# DVforArduino.net
KiCad netlist of a schematic drawn in EAGLE
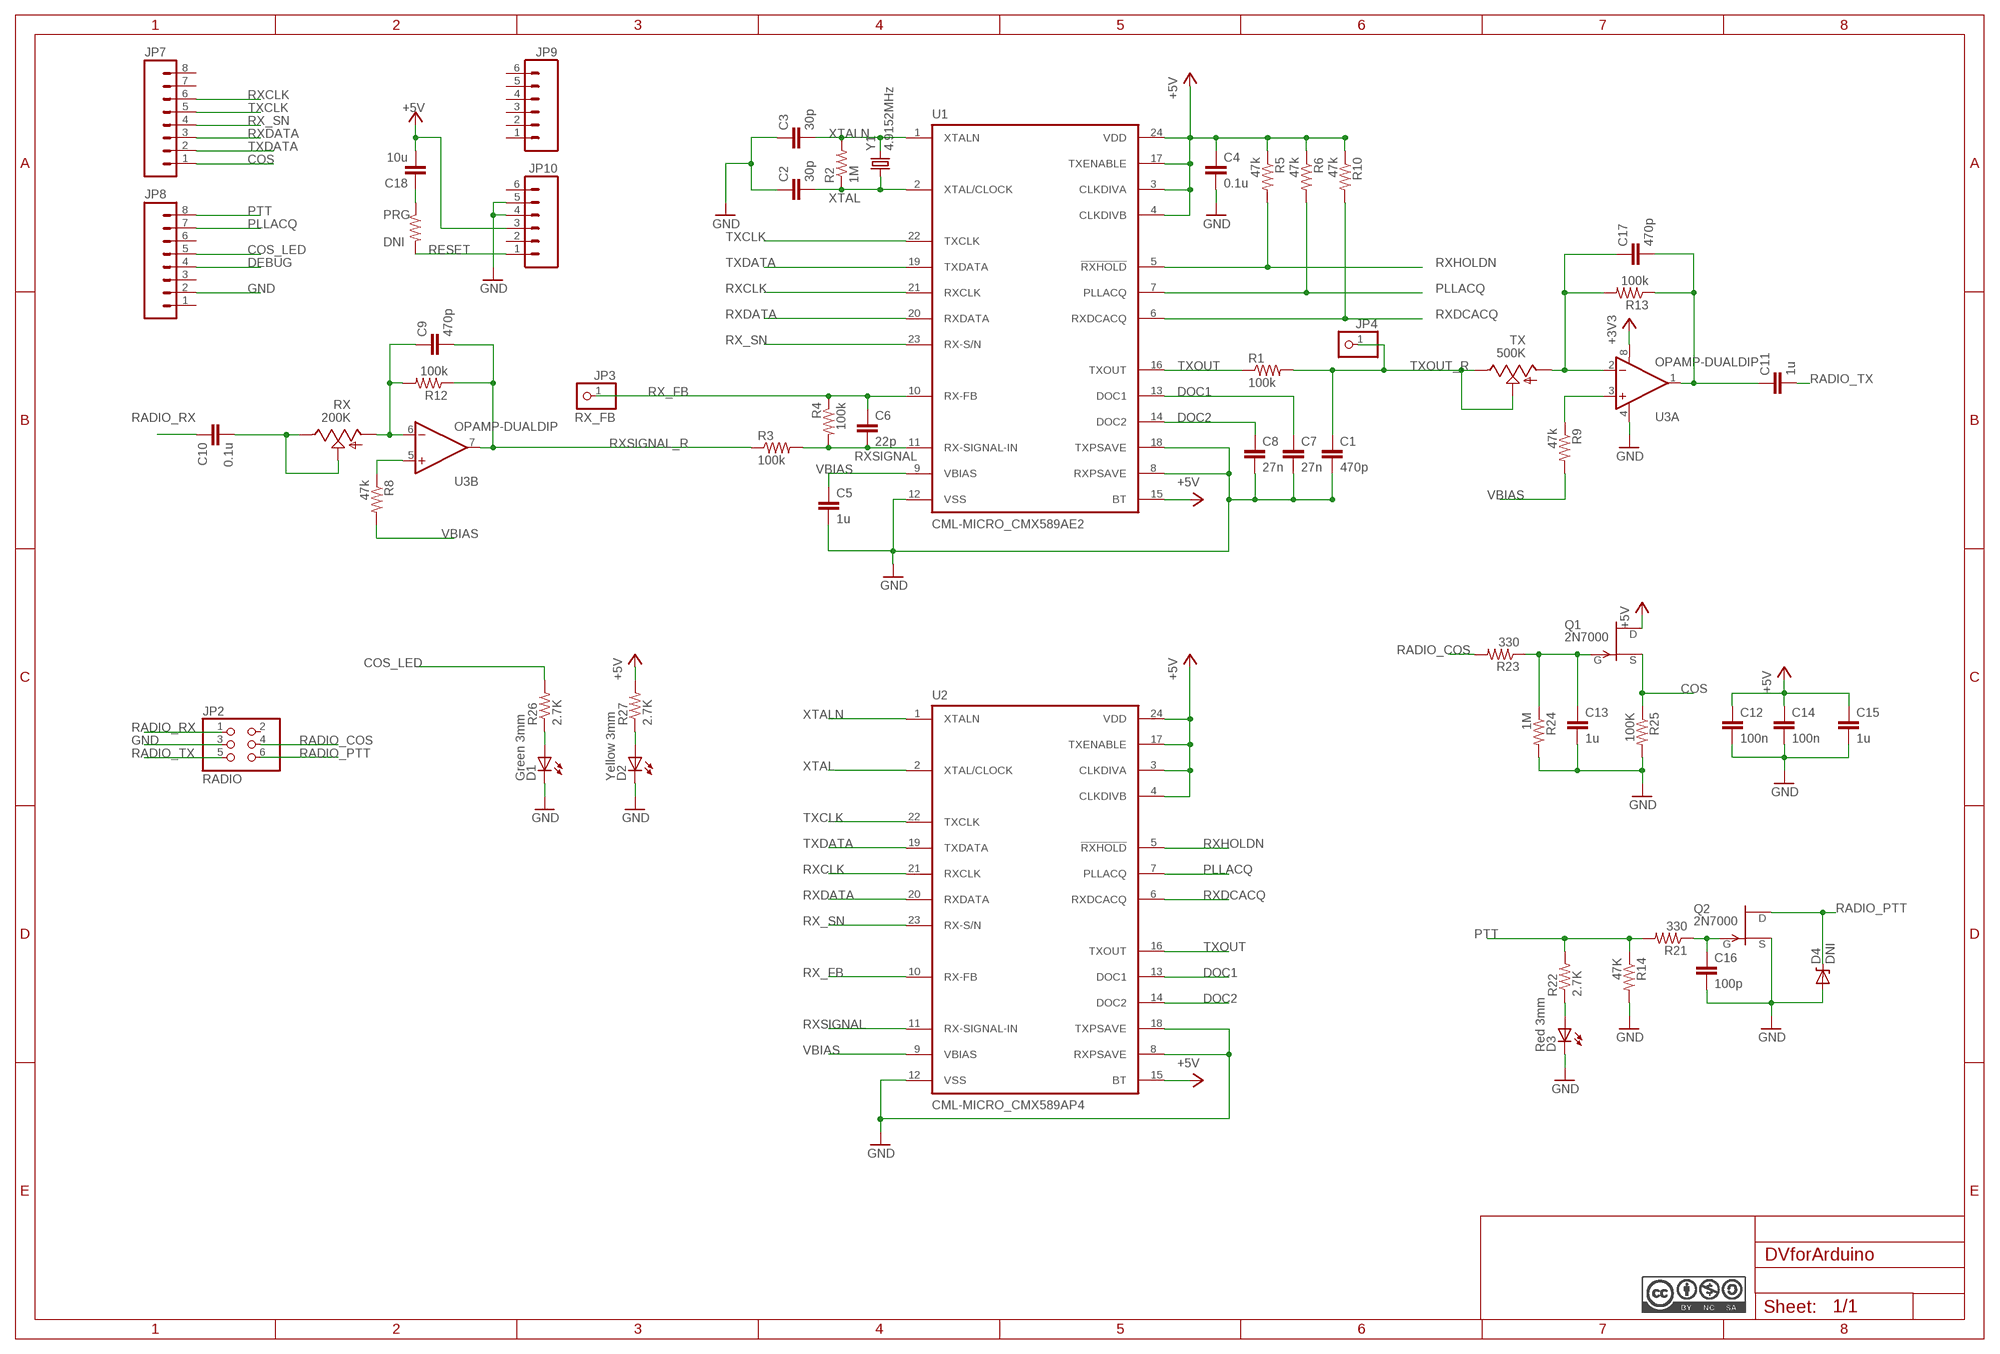
[diagram p0: schematic, sheet 1]

(export (version "E")
  (design (tool "Eeschema 10.0.6"))
  (components
    (comp (ref "C1")
      (value "470p")
      (footprint "eagle-import:C2.5-3")
      (libsource (lib "eagle-import") (part "C2,5-3"))
    )
    (comp (ref "C2")
      (value "30p")
      (footprint "eagle-import:C2.5-3")
      (libsource (lib "eagle-import") (part "C2,5-3"))
    )
    (comp (ref "C3")
      (value "30p")
      (footprint "eagle-import:C2.5-3")
      (libsource (lib "eagle-import") (part "C2,5-3"))
    )
    (comp (ref "C4")
      (value "0.1u")
      (footprint "eagle-import:C2.5-3")
      (libsource (lib "eagle-import") (part "C2,5-3"))
    )
    (comp (ref "C5")
      (value "1u")
      (footprint "eagle-import:C2.5-3")
      (libsource (lib "eagle-import") (part "C2,5-3"))
    )
    (comp (ref "C6")
      (value "22p")
      (footprint "eagle-import:C2.5-3")
      (libsource (lib "eagle-import") (part "C2,5-3"))
    )
    (comp (ref "C7")
      (value "27n")
      (footprint "eagle-import:C2.5-3")
      (libsource (lib "eagle-import") (part "C2,5-3"))
    )
    (comp (ref "C8")
      (value "27n")
      (footprint "eagle-import:C2.5-3")
      (libsource (lib "eagle-import") (part "C2,5-3"))
    )
    (comp (ref "C9")
      (value "470p")
      (footprint "eagle-import:C2.5-3")
      (libsource (lib "eagle-import") (part "C2,5-3"))
    )
    (comp (ref "C10")
      (value "0.1u")
      (footprint "eagle-import:C2.5-3")
      (libsource (lib "eagle-import") (part "C2,5-3"))
    )
    (comp (ref "C11")
      (value "1u")
      (footprint "eagle-import:C2.5-3")
      (libsource (lib "eagle-import") (part "C2,5-3"))
    )
    (comp (ref "C12")
      (value "100n")
      (footprint "eagle-import:C2.5-3")
      (libsource (lib "eagle-import") (part "C2,5-3"))
    )
    (comp (ref "C13")
      (value "1u")
      (footprint "eagle-import:C2.5-3")
      (libsource (lib "eagle-import") (part "C2,5-3"))
    )
    (comp (ref "C14")
      (value "100n")
      (footprint "eagle-import:C2.5-3")
      (libsource (lib "eagle-import") (part "C2,5-3"))
    )
    (comp (ref "C15")
      (value "1u")
      (footprint "eagle-import:C2.5-3")
      (libsource (lib "eagle-import") (part "C2,5-3"))
    )
    (comp (ref "C16")
      (value "100p")
      (footprint "eagle-import:C2.5-3")
      (libsource (lib "eagle-import") (part "C2,5-3"))
    )
    (comp (ref "C17")
      (value "470p")
      (footprint "eagle-import:C2.5-3")
      (libsource (lib "eagle-import") (part "C2,5-3"))
    )
    (comp (ref "C18")
      (value "10u")
      (footprint "eagle-import:C2.5-3")
      (libsource (lib "eagle-import") (part "C2,5-3"))
    )
    (comp (ref "D1")
      (value "Green 3mm")
      (footprint "eagle-import:LED3MM")
      (libsource (lib "eagle-import") (part "LED3MM"))
    )
    (comp (ref "D2")
      (value "Yellow 3mm")
      (footprint "eagle-import:LED3MM")
      (libsource (lib "eagle-import") (part "LED3MM"))
    )
    (comp (ref "D3")
      (value "Red 3mm")
      (footprint "eagle-import:LED3MM")
      (libsource (lib "eagle-import") (part "LED3MM"))
    )
    (comp (ref "D4")
      (value "DNI")
      (footprint "eagle-import:DIODE-ZENER")
      (libsource (lib "eagle-import") (part "DIODE-ZENERPTH"))
    )
    (comp (ref "JP2")
      (value "RADIO")
      (footprint "eagle-import:2X03_ROUND_70MIL")
      (libsource (lib "eagle-import") (part "HEADER-2X3"))
    )
    (comp (ref "JP3")
      (value "RX_FB")
      (footprint "eagle-import:1X01_ROUND")
      (libsource (lib "eagle-import") (part "HEADER-1X1ROUND"))
    )
    (comp (ref "JP4")
      (value "HEADER-1X1ROUND")
      (footprint "eagle-import:1X01_ROUND")
      (libsource (lib "eagle-import") (part "HEADER-1X1ROUND"))
    )
    (comp (ref "JP7")
      (value "M081X08")
      (footprint "eagle-import:1X08")
      (libsource (lib "eagle-import") (part "M081X08"))
    )
    (comp (ref "JP8")
      (value "M081X08")
      (footprint "eagle-import:1X08")
      (libsource (lib "eagle-import") (part "M081X08"))
    )
    (comp (ref "JP9")
      (value "M06SIP")
      (footprint "eagle-import:1X06")
      (libsource (lib "eagle-import") (part "M06SIP"))
    )
    (comp (ref "JP10")
      (value "M06SIP")
      (footprint "eagle-import:1X06")
      (libsource (lib "eagle-import") (part "M06SIP"))
    )
    (comp (ref "PRG")
      (value "DNI")
      (footprint "eagle-import:0204V")
      (libsource (lib "eagle-import") (part "R-US_0204/2V"))
    )
    (comp (ref "Q1")
      (value "2N7000")
      (footprint "eagle-import:TO92")
      (libsource (lib "eagle-import") (part "2N3819"))
    )
    (comp (ref "Q2")
      (value "2N7000")
      (footprint "eagle-import:TO92")
      (libsource (lib "eagle-import") (part "2N3819"))
    )
    (comp (ref "R1")
      (value "100k")
      (footprint "eagle-import:0204V")
      (libsource (lib "eagle-import") (part "R-US_0204/2V"))
    )
    (comp (ref "R2")
      (value "1M")
      (footprint "eagle-import:0204V")
      (libsource (lib "eagle-import") (part "R-US_0204/2V"))
    )
    (comp (ref "R3")
      (value "100k")
      (footprint "eagle-import:0204V")
      (libsource (lib "eagle-import") (part "R-US_0204/2V"))
    )
    (comp (ref "R4")
      (value "100k")
      (footprint "eagle-import:0204V")
      (libsource (lib "eagle-import") (part "R-US_0204/2V"))
    )
    (comp (ref "R5")
      (value "47k")
      (footprint "eagle-import:0204V")
      (libsource (lib "eagle-import") (part "R-US_0204/2V"))
    )
    (comp (ref "R6")
      (value "47k")
      (footprint "eagle-import:0204V")
      (libsource (lib "eagle-import") (part "R-US_0204/2V"))
    )
    (comp (ref "R8")
      (value "47k")
      (footprint "eagle-import:0204V")
      (libsource (lib "eagle-import") (part "R-US_0204/2V"))
    )
    (comp (ref "R9")
      (value "47k")
      (footprint "eagle-import:0204V")
      (libsource (lib "eagle-import") (part "R-US_0204/2V"))
    )
    (comp (ref "R10")
      (value "47k")
      (footprint "eagle-import:0204V")
      (libsource (lib "eagle-import") (part "R-US_0204/2V"))
    )
    (comp (ref "R12")
      (value "100k")
      (footprint "eagle-import:0204V")
      (libsource (lib "eagle-import") (part "R-US_0204/2V"))
    )
    (comp (ref "R13")
      (value "100k")
      (footprint "eagle-import:0204V")
      (libsource (lib "eagle-import") (part "R-US_0204/2V"))
    )
    (comp (ref "R14")
      (value "47K")
      (footprint "eagle-import:0204V")
      (libsource (lib "eagle-import") (part "R-US_0204/2V"))
    )
    (comp (ref "R21")
      (value "330")
      (footprint "eagle-import:0204V")
      (libsource (lib "eagle-import") (part "R-US_0204/2V"))
    )
    (comp (ref "R22")
      (value "2.7K")
      (footprint "eagle-import:0204V")
      (libsource (lib "eagle-import") (part "R-US_0204/2V"))
    )
    (comp (ref "R23")
      (value "330")
      (footprint "eagle-import:0204V")
      (libsource (lib "eagle-import") (part "R-US_0204/2V"))
    )
    (comp (ref "R24")
      (value "1M")
      (footprint "eagle-import:0204V")
      (libsource (lib "eagle-import") (part "R-US_0204/2V"))
    )
    (comp (ref "R25")
      (value "100K")
      (footprint "eagle-import:0204V")
      (libsource (lib "eagle-import") (part "R-US_0204/2V"))
    )
    (comp (ref "R26")
      (value "2.7K")
      (footprint "eagle-import:0204V")
      (libsource (lib "eagle-import") (part "R-US_0204/2V"))
    )
    (comp (ref "R27")
      (value "2.7K")
      (footprint "eagle-import:0204V")
      (libsource (lib "eagle-import") (part "R-US_0204/2V"))
    )
    (comp (ref "RX")
      (value "200K")
      (footprint "eagle-import:B25P")
      (libsource (lib "eagle-import") (part "TRIM_US-B25P"))
    )
    (comp (ref "TX")
      (value "500K")
      (footprint "eagle-import:B25P")
      (libsource (lib "eagle-import") (part "TRIM_US-B25P"))
    )
    (comp (ref "U1")
      (value "CML-MICRO_CMX589AE2")
      (footprint "eagle-import:AIS_MK2_CML-MICRO_TSSOP24")
      (libsource (lib "eagle-import") (part "mylibrary_AIS_MK2_CML-MICRO_CMX589AE2"))
    )
    (comp (ref "U2")
      (value "CML-MICRO_CMX589AP4")
      (footprint "eagle-import:AIS_MK2_CML-MICRO_DIL24-6")
      (libsource (lib "eagle-import") (part "AIS_MK2_CML-MICRO_CMX589AP4"))
    )
    (comp (ref "U3")
      (value "OPAMP-DUALDIP")
      (footprint "eagle-import:DIP08")
      (libsource (lib "eagle-import") (part "OPAMP-DUALDIP"))
    )
    (comp (ref "Y1")
      (value "4.9152MHz")
      (footprint "eagle-import:HC49US")
      (libsource (lib "eagle-import") (part "CRYSTALHC49US"))
    )
  )
  (nets
    (net (code "1") (name "+3V3") (class "Default")
      (node (ref "C12") (pin "1") (pinfunction "1_1") (pintype "passive"))
      (node (ref "C14") (pin "1") (pinfunction "1_1") (pintype "passive"))
      (node (ref "C15") (pin "1") (pinfunction "1_1") (pintype "passive"))
      (node (ref "C18") (pin "2") (pinfunction "2_2") (pintype "passive"))
      (node (ref "C4") (pin "1") (pinfunction "1_1") (pintype "passive"))
      (node (ref "JP10") (pin "3") (pinfunction "3_3") (pintype "passive"))
      (node (ref "Q1") (pin "1") (pinfunction "D_1") (pintype "passive"))
      (node (ref "R10") (pin "1") (pinfunction "1_1") (pintype "passive"))
      (node (ref "R27") (pin "2") (pinfunction "2_2") (pintype "passive"))
      (node (ref "R5") (pin "1") (pinfunction "1_1") (pintype "passive"))
      (node (ref "R6") (pin "1") (pinfunction "1_1") (pintype "passive"))
      (node (ref "U1") (pin "15") (pinfunction "BT_15") (pintype "input"))
      (node (ref "U1") (pin "17") (pinfunction "TXENABLE_17") (pintype "input"))
      (node (ref "U1") (pin "24") (pinfunction "VDD_24") (pintype "power_in"))
      (node (ref "U1") (pin "3") (pinfunction "CLKDIVA_3") (pintype "input"))
      (node (ref "U1") (pin "4") (pinfunction "CLKDIVB_4") (pintype "input"))
      (node (ref "U2") (pin "15") (pinfunction "BT_15") (pintype "input"))
      (node (ref "U2") (pin "17") (pinfunction "TXENABLE_17") (pintype "input"))
      (node (ref "U2") (pin "24") (pinfunction "VDD_24") (pintype "power_in"))
      (node (ref "U2") (pin "3") (pinfunction "CLKDIVA_3") (pintype "input"))
      (node (ref "U2") (pin "4") (pinfunction "CLKDIVB_4") (pintype "input"))
      (node (ref "U3") (pin "8") (pinfunction "V+_8") (pintype "power_in"))
    )
    (net (code "2") (name "/COS") (class "Default")
      (node (ref "JP7") (pin "1") (pinfunction "1_1") (pintype "passive"))
      (node (ref "Q1") (pin "3") (pinfunction "S_3") (pintype "passive"))
      (node (ref "R25") (pin "1") (pinfunction "1_1") (pintype "passive"))
    )
    (net (code "3") (name "/COS_LED") (class "Default")
      (node (ref "JP8") (pin "5") (pinfunction "5_5") (pintype "passive"))
      (node (ref "R26") (pin "2") (pinfunction "2_2") (pintype "passive"))
    )
    (net (code "4") (name "/DEBUG") (class "Default")
      (node (ref "JP8") (pin "4") (pinfunction "4_4") (pintype "passive"))
    )
    (net (code "5") (name "/DOC1") (class "Default")
      (node (ref "C7") (pin "1") (pinfunction "1_1") (pintype "passive"))
      (node (ref "U1") (pin "13") (pinfunction "DOC1_13") (pintype "passive"))
      (node (ref "U2") (pin "13") (pinfunction "DOC1_13") (pintype "passive"))
    )
    (net (code "6") (name "/DOC2") (class "Default")
      (node (ref "C8") (pin "1") (pinfunction "1_1") (pintype "passive"))
      (node (ref "U1") (pin "14") (pinfunction "DOC2_14") (pintype "passive"))
      (node (ref "U2") (pin "14") (pinfunction "DOC2_14") (pintype "passive"))
    )
    (net (code "7") (name "/PLLACQ") (class "Default")
      (node (ref "JP8") (pin "7") (pinfunction "7_7") (pintype "passive"))
      (node (ref "R6") (pin "2") (pinfunction "2_2") (pintype "passive"))
      (node (ref "U1") (pin "7") (pinfunction "PLLACQ_7") (pintype "input"))
      (node (ref "U2") (pin "7") (pinfunction "PLLACQ_7") (pintype "input"))
    )
    (net (code "8") (name "/PTT") (class "Default")
      (node (ref "JP8") (pin "8") (pinfunction "8_8") (pintype "passive"))
      (node (ref "R14") (pin "1") (pinfunction "1_1") (pintype "passive"))
      (node (ref "R21") (pin "2") (pinfunction "2_2") (pintype "passive"))
      (node (ref "R22") (pin "2") (pinfunction "2_2") (pintype "passive"))
    )
    (net (code "9") (name "/RADIO_COS") (class "Default")
      (node (ref "JP2") (pin "4") (pinfunction "4_4") (pintype "passive"))
      (node (ref "R23") (pin "2") (pinfunction "2_2") (pintype "passive"))
    )
    (net (code "10") (name "/RADIO_PTT") (class "Default")
      (node (ref "D4") (pin "P$1") (pinfunction "C_P$1") (pintype "passive"))
      (node (ref "JP2") (pin "6") (pinfunction "6_6") (pintype "passive"))
      (node (ref "Q2") (pin "1") (pinfunction "D_1") (pintype "passive"))
    )
    (net (code "11") (name "/RADIO_RX") (class "Default")
      (node (ref "C10") (pin "1") (pinfunction "1_1") (pintype "passive"))
      (node (ref "JP2") (pin "1") (pinfunction "1_1") (pintype "passive"))
    )
    (net (code "12") (name "/RADIO_TX") (class "Default")
      (node (ref "C11") (pin "2") (pinfunction "2_2") (pintype "passive"))
      (node (ref "JP2") (pin "5") (pinfunction "5_5") (pintype "passive"))
    )
    (net (code "13") (name "/RESET") (class "Default")
      (node (ref "JP10") (pin "1") (pinfunction "1_1") (pintype "passive"))
      (node (ref "PRG") (pin "2") (pinfunction "2_2") (pintype "passive"))
    )
    (net (code "14") (name "/RXCLK") (class "Default")
      (node (ref "JP7") (pin "6") (pinfunction "6_6") (pintype "passive"))
      (node (ref "U1") (pin "21") (pinfunction "RXCLK_21") (pintype "output"))
      (node (ref "U2") (pin "21") (pinfunction "RXCLK_21") (pintype "output"))
    )
    (net (code "15") (name "/RXDATA") (class "Default")
      (node (ref "JP7") (pin "3") (pinfunction "3_3") (pintype "passive"))
      (node (ref "U1") (pin "20") (pinfunction "RXDATA_20") (pintype "output"))
      (node (ref "U2") (pin "20") (pinfunction "RXDATA_20") (pintype "output"))
    )
    (net (code "16") (name "/RXDCACQ") (class "Default")
      (node (ref "R10") (pin "2") (pinfunction "2_2") (pintype "passive"))
      (node (ref "U1") (pin "6") (pinfunction "RXDCACQ_6") (pintype "input"))
      (node (ref "U2") (pin "6") (pinfunction "RXDCACQ_6") (pintype "input"))
    )
    (net (code "17") (name "/RXHOLDN") (class "Default")
      (node (ref "R5") (pin "2") (pinfunction "2_2") (pintype "passive"))
      (node (ref "U1") (pin "5") (pinfunction "~{RXHOLD}_5") (pintype "input"))
      (node (ref "U2") (pin "5") (pinfunction "~{RXHOLD}_5") (pintype "input"))
    )
    (net (code "18") (name "/RXSIGNAL") (class "Default")
      (node (ref "C6") (pin "2") (pinfunction "2_2") (pintype "passive"))
      (node (ref "R3") (pin "2") (pinfunction "2_2") (pintype "passive"))
      (node (ref "R4") (pin "2") (pinfunction "2_2") (pintype "passive"))
      (node (ref "U1") (pin "11") (pinfunction "RX-SIGNAL-IN_11") (pintype "input"))
      (node (ref "U2") (pin "11") (pinfunction "RX-SIGNAL-IN_11") (pintype "input"))
    )
    (net (code "19") (name "/RXSIGNAL_R") (class "Default")
      (node (ref "C9") (pin "2") (pinfunction "2_2") (pintype "passive"))
      (node (ref "R12") (pin "1") (pinfunction "1_1") (pintype "passive"))
      (node (ref "R3") (pin "1") (pinfunction "1_1") (pintype "passive"))
      (node (ref "U3") (pin "7") (pinfunction "OUT_7") (pintype "output"))
    )
    (net (code "20") (name "/RX_FB") (class "Default")
      (node (ref "C6") (pin "1") (pinfunction "1_1") (pintype "passive"))
      (node (ref "JP3") (pin "1") (pinfunction "1_1") (pintype "passive"))
      (node (ref "R4") (pin "1") (pinfunction "1_1") (pintype "passive"))
      (node (ref "U1") (pin "10") (pinfunction "RX-FB_10") (pintype "input"))
      (node (ref "U2") (pin "10") (pinfunction "RX-FB_10") (pintype "input"))
    )
    (net (code "21") (name "/RX_SN") (class "Default")
      (node (ref "JP7") (pin "4") (pinfunction "4_4") (pintype "passive"))
      (node (ref "U1") (pin "23") (pinfunction "RX-S/N_23") (pintype "output"))
      (node (ref "U2") (pin "23") (pinfunction "RX-S/N_23") (pintype "output"))
    )
    (net (code "22") (name "/TXCLK") (class "Default")
      (node (ref "JP7") (pin "5") (pinfunction "5_5") (pintype "passive"))
      (node (ref "U1") (pin "22") (pinfunction "TXCLK_22") (pintype "output"))
      (node (ref "U2") (pin "22") (pinfunction "TXCLK_22") (pintype "output"))
    )
    (net (code "23") (name "/TXDATA") (class "Default")
      (node (ref "JP7") (pin "2") (pinfunction "2_2") (pintype "passive"))
      (node (ref "U1") (pin "19") (pinfunction "TXDATA_19") (pintype "input"))
      (node (ref "U2") (pin "19") (pinfunction "TXDATA_19") (pintype "input"))
    )
    (net (code "24") (name "/TXOUT") (class "Default")
      (node (ref "R1") (pin "1") (pinfunction "1_1") (pintype "passive"))
      (node (ref "U1") (pin "16") (pinfunction "TXOUT_16") (pintype "output"))
      (node (ref "U2") (pin "16") (pinfunction "TXOUT_16") (pintype "output"))
    )
    (net (code "25") (name "/TXOUT_R") (class "Default")
      (node (ref "C1") (pin "1") (pinfunction "1_1") (pintype "passive"))
      (node (ref "JP4") (pin "1") (pinfunction "1_1") (pintype "passive"))
      (node (ref "R1") (pin "2") (pinfunction "2_2") (pintype "passive"))
      (node (ref "TX") (pin "E") (pinfunction "E_E") (pintype "passive"))
      (node (ref "TX") (pin "S") (pinfunction "S_S") (pintype "passive"))
    )
    (net (code "26") (name "/VBIAS") (class "Default")
      (node (ref "C5") (pin "1") (pinfunction "1_1") (pintype "passive"))
      (node (ref "R8") (pin "2") (pinfunction "2_2") (pintype "passive"))
      (node (ref "R9") (pin "2") (pinfunction "2_2") (pintype "passive"))
      (node (ref "U1") (pin "9") (pinfunction "VBIAS_9") (pintype "input"))
      (node (ref "U2") (pin "9") (pinfunction "VBIAS_9") (pintype "input"))
    )
    (net (code "27") (name "/XTAL") (class "Default")
      (node (ref "C2") (pin "2") (pinfunction "2_2") (pintype "passive"))
      (node (ref "R2") (pin "1") (pinfunction "1_1") (pintype "passive"))
      (node (ref "U1") (pin "2") (pinfunction "XTAL/CLOCK_2") (pintype "input"))
      (node (ref "U2") (pin "2") (pinfunction "XTAL/CLOCK_2") (pintype "input"))
      (node (ref "Y1") (pin "1") (pinfunction "1_1") (pintype "passive"))
    )
    (net (code "28") (name "/XTALN") (class "Default")
      (node (ref "C3") (pin "2") (pinfunction "2_2") (pintype "passive"))
      (node (ref "R2") (pin "2") (pinfunction "2_2") (pintype "passive"))
      (node (ref "U1") (pin "1") (pinfunction "XTALN_1") (pintype "output"))
      (node (ref "U2") (pin "1") (pinfunction "XTALN_1") (pintype "output"))
      (node (ref "Y1") (pin "2") (pinfunction "2_2") (pintype "passive"))
    )
    (net (code "29") (name "GND") (class "Default")
      (node (ref "C1") (pin "2") (pinfunction "2_2") (pintype "passive"))
      (node (ref "C12") (pin "2") (pinfunction "2_2") (pintype "passive"))
      (node (ref "C13") (pin "2") (pinfunction "2_2") (pintype "passive"))
      (node (ref "C14") (pin "2") (pinfunction "2_2") (pintype "passive"))
      (node (ref "C15") (pin "2") (pinfunction "2_2") (pintype "passive"))
      (node (ref "C16") (pin "2") (pinfunction "2_2") (pintype "passive"))
      (node (ref "C2") (pin "1") (pinfunction "1_1") (pintype "passive"))
      (node (ref "C3") (pin "1") (pinfunction "1_1") (pintype "passive"))
      (node (ref "C4") (pin "2") (pinfunction "2_2") (pintype "passive"))
      (node (ref "C5") (pin "2") (pinfunction "2_2") (pintype "passive"))
      (node (ref "C7") (pin "2") (pinfunction "2_2") (pintype "passive"))
      (node (ref "C8") (pin "2") (pinfunction "2_2") (pintype "passive"))
      (node (ref "D1") (pin "K") (pinfunction "C_K") (pintype "passive"))
      (node (ref "D2") (pin "K") (pinfunction "C_K") (pintype "passive"))
      (node (ref "D3") (pin "K") (pinfunction "C_K") (pintype "passive"))
      (node (ref "D4") (pin "P$2") (pinfunction "A_P$2") (pintype "passive"))
      (node (ref "JP10") (pin "4") (pinfunction "4_4") (pintype "passive"))
      (node (ref "JP10") (pin "5") (pinfunction "5_5") (pintype "passive"))
      (node (ref "JP2") (pin "3") (pinfunction "3_3") (pintype "passive"))
      (node (ref "JP8") (pin "2") (pinfunction "2_2") (pintype "passive"))
      (node (ref "Q2") (pin "3") (pinfunction "S_3") (pintype "passive"))
      (node (ref "R14") (pin "2") (pinfunction "2_2") (pintype "passive"))
      (node (ref "R24") (pin "2") (pinfunction "2_2") (pintype "passive"))
      (node (ref "R25") (pin "2") (pinfunction "2_2") (pintype "passive"))
      (node (ref "U1") (pin "12") (pinfunction "VSS_12") (pintype "power_in"))
      (node (ref "U1") (pin "18") (pinfunction "TXPSAVE_18") (pintype "input"))
      (node (ref "U1") (pin "8") (pinfunction "RXPSAVE_8") (pintype "input"))
      (node (ref "U2") (pin "12") (pinfunction "VSS_12") (pintype "power_in"))
      (node (ref "U2") (pin "18") (pinfunction "TXPSAVE_18") (pintype "input"))
      (node (ref "U2") (pin "8") (pinfunction "RXPSAVE_8") (pintype "input"))
      (node (ref "U3") (pin "4") (pinfunction "V-_4") (pintype "power_in"))
    )
    (net (code "30") (name "Net-(C10-Pad2)") (class "Default")
      (node (ref "C10") (pin "2") (pinfunction "2_2") (pintype "passive"))
      (node (ref "RX") (pin "E") (pinfunction "E_E") (pintype "passive"))
      (node (ref "RX") (pin "S") (pinfunction "S_S") (pintype "passive"))
    )
    (net (code "31") (name "Net-(C18-Pad1)") (class "Default")
      (node (ref "C18") (pin "1") (pinfunction "1_1") (pintype "passive"))
      (node (ref "PRG") (pin "1") (pinfunction "1_1") (pintype "passive"))
    )
    (net (code "32") (name "Net-(D1-PadA)") (class "Default")
      (node (ref "D1") (pin "A") (pinfunction "A_A") (pintype "passive"))
      (node (ref "R26") (pin "1") (pinfunction "1_1") (pintype "passive"))
    )
    (net (code "33") (name "Net-(D2-PadA)") (class "Default")
      (node (ref "D2") (pin "A") (pinfunction "A_A") (pintype "passive"))
      (node (ref "R27") (pin "1") (pinfunction "1_1") (pintype "passive"))
    )
    (net (code "34") (name "Net-(D3-PadA)") (class "Default")
      (node (ref "D3") (pin "A") (pinfunction "A_A") (pintype "passive"))
      (node (ref "R22") (pin "1") (pinfunction "1_1") (pintype "passive"))
    )
    (net (code "35") (name "Net-(Q1-G)") (class "Default")
      (node (ref "C13") (pin "1") (pinfunction "1_1") (pintype "passive"))
      (node (ref "Q1") (pin "2") (pinfunction "G_2") (pintype "passive"))
      (node (ref "R23") (pin "1") (pinfunction "1_1") (pintype "passive"))
      (node (ref "R24") (pin "1") (pinfunction "1_1") (pintype "passive"))
    )
    (net (code "36") (name "Net-(Q2-G)") (class "Default")
      (node (ref "C16") (pin "1") (pinfunction "1_1") (pintype "passive"))
      (node (ref "Q2") (pin "2") (pinfunction "G_2") (pintype "passive"))
      (node (ref "R21") (pin "1") (pinfunction "1_1") (pintype "passive"))
    )
    (net (code "37") (name "Net-(U3A-+IN)") (class "Default")
      (node (ref "R9") (pin "1") (pinfunction "1_1") (pintype "passive"))
      (node (ref "U3") (pin "3") (pinfunction "+IN_3") (pintype "input"))
    )
    (net (code "38") (name "Net-(U3A--IN)") (class "Default")
      (node (ref "C17") (pin "1") (pinfunction "1_1") (pintype "passive"))
      (node (ref "R13") (pin "2") (pinfunction "2_2") (pintype "passive"))
      (node (ref "TX") (pin "A") (pinfunction "A_A") (pintype "passive"))
      (node (ref "U3") (pin "2") (pinfunction "-IN_2") (pintype "input"))
    )
    (net (code "39") (name "Net-(U3A-OUT)") (class "Default")
      (node (ref "C11") (pin "1") (pinfunction "1_1") (pintype "passive"))
      (node (ref "C17") (pin "2") (pinfunction "2_2") (pintype "passive"))
      (node (ref "R13") (pin "1") (pinfunction "1_1") (pintype "passive"))
      (node (ref "U3") (pin "1") (pinfunction "OUT_1") (pintype "output"))
    )
    (net (code "40") (name "Net-(U3B-+IN)") (class "Default")
      (node (ref "R8") (pin "1") (pinfunction "1_1") (pintype "passive"))
      (node (ref "U3") (pin "5") (pinfunction "+IN_5") (pintype "input"))
    )
    (net (code "41") (name "Net-(U3B--IN)") (class "Default")
      (node (ref "C9") (pin "1") (pinfunction "1_1") (pintype "passive"))
      (node (ref "R12") (pin "2") (pinfunction "2_2") (pintype "passive"))
      (node (ref "RX") (pin "A") (pinfunction "A_A") (pintype "passive"))
      (node (ref "U3") (pin "6") (pinfunction "-IN_6") (pintype "input"))
    )
    (net (code "42") (name "unconnected-(JP2-Pad2)") (class "Default")
      (node (ref "JP2") (pin "2") (pinfunction "2_2") (pintype "passive"))
    )
    (net (code "43") (name "unconnected-(JP7-Pad7)") (class "Default")
      (node (ref "JP7") (pin "7") (pinfunction "7_7") (pintype "passive"))
    )
    (net (code "44") (name "unconnected-(JP7-Pad8)") (class "Default")
      (node (ref "JP7") (pin "8") (pinfunction "8_8") (pintype "passive"))
    )
    (net (code "45") (name "unconnected-(JP8-Pad1)") (class "Default")
      (node (ref "JP8") (pin "1") (pinfunction "1_1") (pintype "passive"))
    )
    (net (code "46") (name "unconnected-(JP8-Pad3)") (class "Default")
      (node (ref "JP8") (pin "3") (pinfunction "3_3") (pintype "passive"))
    )
    (net (code "47") (name "unconnected-(JP8-Pad6)") (class "Default")
      (node (ref "JP8") (pin "6") (pinfunction "6_6") (pintype "passive"))
    )
    (net (code "48") (name "unconnected-(JP9-Pad1)") (class "Default")
      (node (ref "JP9") (pin "1") (pinfunction "1_1") (pintype "passive"))
    )
    (net (code "49") (name "unconnected-(JP9-Pad2)") (class "Default")
      (node (ref "JP9") (pin "2") (pinfunction "2_2") (pintype "passive"))
    )
    (net (code "50") (name "unconnected-(JP9-Pad3)") (class "Default")
      (node (ref "JP9") (pin "3") (pinfunction "3_3") (pintype "passive"))
    )
    (net (code "51") (name "unconnected-(JP9-Pad4)") (class "Default")
      (node (ref "JP9") (pin "4") (pinfunction "4_4") (pintype "passive"))
    )
    (net (code "52") (name "unconnected-(JP9-Pad5)") (class "Default")
      (node (ref "JP9") (pin "5") (pinfunction "5_5") (pintype "passive"))
    )
    (net (code "53") (name "unconnected-(JP9-Pad6)") (class "Default")
      (node (ref "JP9") (pin "6") (pinfunction "6_6") (pintype "passive"))
    )
    (net (code "54") (name "unconnected-(JP10-Pad2)") (class "Default")
      (node (ref "JP10") (pin "2") (pinfunction "2_2") (pintype "passive"))
    )
    (net (code "55") (name "unconnected-(JP10-Pad6)") (class "Default")
      (node (ref "JP10") (pin "6") (pinfunction "6_6") (pintype "passive"))
    )
  )
)
